# base.net
KiCad netlist of a schematic drawn in EAGLE
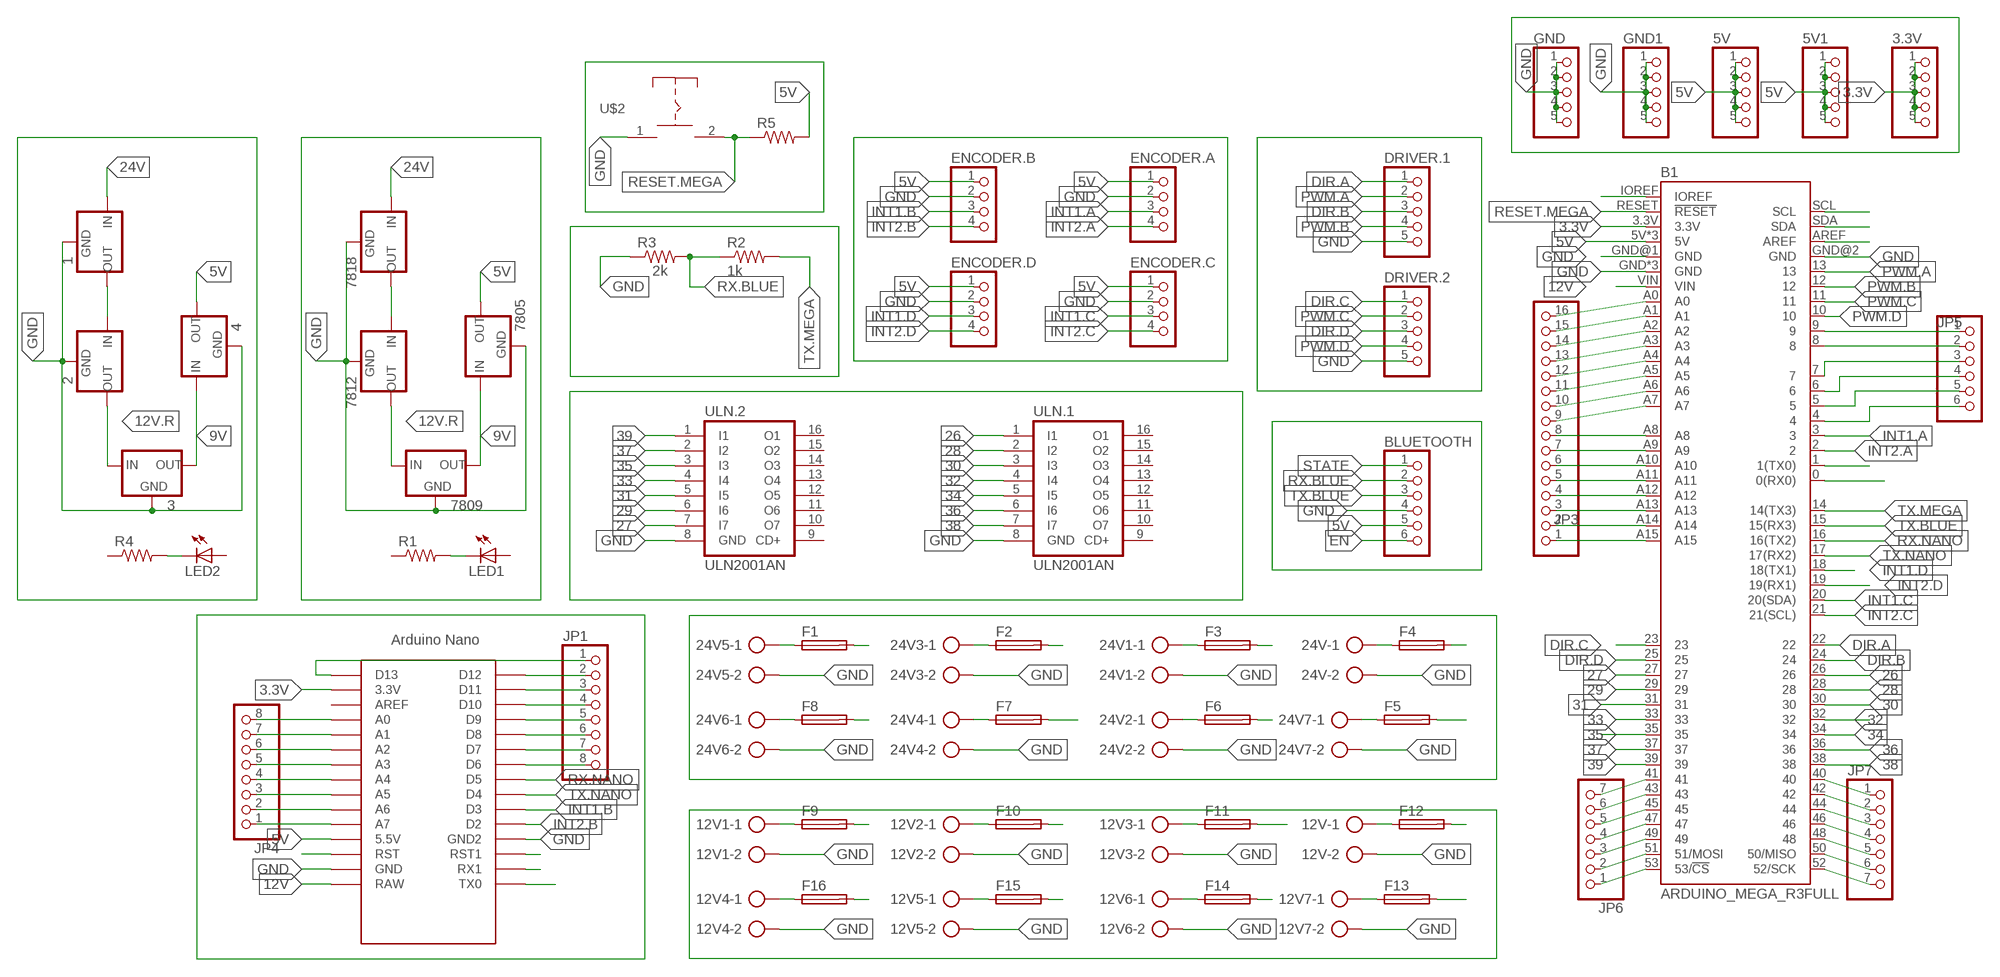
[diagram p0: schematic, sheet 1]

(export (version "E")
  (design (tool "Eeschema 10.0.6"))
  (components
    (comp (ref "1")
      (value "78XXS")
      (footprint "eagle-import:78XXS")
      (libsource (lib "eagle-import") (part "78XXS"))
    )
    (comp (ref "2")
      (value "78XXS")
      (footprint "eagle-import:78XXS")
      (libsource (lib "eagle-import") (part "78XXS"))
    )
    (comp (ref "3")
      (value "78XXS")
      (footprint "eagle-import:78XXS")
      (libsource (lib "eagle-import") (part "78XXS"))
    )
    (comp (ref "3.3V")
      (value "PINHD-1X5")
      (footprint "eagle-import:1X05")
      (libsource (lib "eagle-import") (part "PINHD-1X5"))
    )
    (comp (ref "4")
      (value "78XXS")
      (footprint "eagle-import:78XXS")
      (libsource (lib "eagle-import") (part "78XXS"))
    )
    (comp (ref "5V")
      (value "PINHD-1X5")
      (footprint "eagle-import:1X05")
      (libsource (lib "eagle-import") (part "PINHD-1X5"))
    )
    (comp (ref "5V1")
      (value "PINHD-1X5")
      (footprint "eagle-import:1X05")
      (libsource (lib "eagle-import") (part "PINHD-1X5"))
    )
    (comp (ref "12V")
      (value "AK300/2")
      (footprint "eagle-import:AK300_2")
      (libsource (lib "eagle-import") (part "AK300/2"))
    )
    (comp (ref "12V1")
      (value "AK300/2")
      (footprint "eagle-import:AK300_2")
      (libsource (lib "eagle-import") (part "AK300/2"))
    )
    (comp (ref "12V2")
      (value "AK300/2")
      (footprint "eagle-import:AK300_2")
      (libsource (lib "eagle-import") (part "AK300/2"))
    )
    (comp (ref "12V3")
      (value "AK300/2")
      (footprint "eagle-import:AK300_2")
      (libsource (lib "eagle-import") (part "AK300/2"))
    )
    (comp (ref "12V4")
      (value "AK300/2")
      (footprint "eagle-import:AK300_2")
      (libsource (lib "eagle-import") (part "AK300/2"))
    )
    (comp (ref "12V5")
      (value "AK300/2")
      (footprint "eagle-import:AK300_2")
      (libsource (lib "eagle-import") (part "AK300/2"))
    )
    (comp (ref "12V6")
      (value "AK300/2")
      (footprint "eagle-import:AK300_2")
      (libsource (lib "eagle-import") (part "AK300/2"))
    )
    (comp (ref "12V7")
      (value "AK300/2")
      (footprint "eagle-import:AK300_2")
      (libsource (lib "eagle-import") (part "AK300/2"))
    )
    (comp (ref "24V")
      (value "AK300/2")
      (footprint "eagle-import:AK300_2")
      (libsource (lib "eagle-import") (part "AK300/2"))
    )
    (comp (ref "24V1")
      (value "AK300/2")
      (footprint "eagle-import:AK300_2")
      (libsource (lib "eagle-import") (part "AK300/2"))
    )
    (comp (ref "24V2")
      (value "AK300/2")
      (footprint "eagle-import:AK300_2")
      (libsource (lib "eagle-import") (part "AK300/2"))
    )
    (comp (ref "24V3")
      (value "AK300/2")
      (footprint "eagle-import:AK300_2")
      (libsource (lib "eagle-import") (part "AK300/2"))
    )
    (comp (ref "24V4")
      (value "AK300/2")
      (footprint "eagle-import:AK300_2")
      (libsource (lib "eagle-import") (part "AK300/2"))
    )
    (comp (ref "24V5")
      (value "AK300/2")
      (footprint "eagle-import:AK300_2")
      (libsource (lib "eagle-import") (part "AK300/2"))
    )
    (comp (ref "24V6")
      (value "AK300/2")
      (footprint "eagle-import:AK300_2")
      (libsource (lib "eagle-import") (part "AK300/2"))
    )
    (comp (ref "24V7")
      (value "AK300/2")
      (footprint "eagle-import:AK300_2")
      (libsource (lib "eagle-import") (part "AK300/2"))
    )
    (comp (ref "7805")
      (value "78XXS")
      (footprint "eagle-import:78XXS")
      (libsource (lib "eagle-import") (part "78XXS"))
    )
    (comp (ref "7809")
      (value "78XXS")
      (footprint "eagle-import:78XXS")
      (libsource (lib "eagle-import") (part "78XXS"))
    )
    (comp (ref "7812")
      (value "78XXS")
      (footprint "eagle-import:78XXS")
      (libsource (lib "eagle-import") (part "78XXS"))
    )
    (comp (ref "7818")
      (value "78XXS")
      (footprint "eagle-import:78XXS")
      (libsource (lib "eagle-import") (part "78XXS"))
    )
    (comp (ref "B1")
      (value "ARDUINO_MEGA_R3FULL")
      (footprint "eagle-import:ARDUINO_MEGA_NO_SILK")
      (libsource (lib "eagle-import") (part "ARDUINO_MEGA_R3FULL"))
    )
    (comp (ref "BLUETOOTH")
      (value "PINHD-1X6")
      (footprint "eagle-import:1X06")
      (libsource (lib "eagle-import") (part "PINHD-1X6"))
    )
    (comp (ref "DRIVER.1")
      (value "PINHD-1X5")
      (footprint "eagle-import:1X05")
      (libsource (lib "eagle-import") (part "PINHD-1X5"))
    )
    (comp (ref "DRIVER.2")
      (value "PINHD-1X5")
      (footprint "eagle-import:1X05")
      (libsource (lib "eagle-import") (part "PINHD-1X5"))
    )
    (comp (ref "ENCODER.A")
      (value "PINHD-1X4")
      (footprint "eagle-import:1X04")
      (libsource (lib "eagle-import") (part "PINHD-1X4"))
    )
    (comp (ref "ENCODER.B")
      (value "PINHD-1X4")
      (footprint "eagle-import:1X04")
      (libsource (lib "eagle-import") (part "PINHD-1X4"))
    )
    (comp (ref "ENCODER.C")
      (value "PINHD-1X4")
      (footprint "eagle-import:1X04")
      (libsource (lib "eagle-import") (part "PINHD-1X4"))
    )
    (comp (ref "ENCODER.D")
      (value "PINHD-1X4")
      (footprint "eagle-import:1X04")
      (libsource (lib "eagle-import") (part "PINHD-1X4"))
    )
    (comp (ref "F1")
      (value "GSH15")
      (footprint "eagle-import:GSH15")
      (fields (field (name "MPN") "64900001039"))
      (libsource (lib "eagle-import") (part "GSH15"))
    )
    (comp (ref "F2")
      (value "GSH15")
      (footprint "eagle-import:GSH15")
      (fields (field (name "MPN") "64900001039"))
      (libsource (lib "eagle-import") (part "GSH15"))
    )
    (comp (ref "F3")
      (value "GSH15")
      (footprint "eagle-import:GSH15")
      (fields (field (name "MPN") "64900001039"))
      (libsource (lib "eagle-import") (part "GSH15"))
    )
    (comp (ref "F4")
      (value "GSH15")
      (footprint "eagle-import:GSH15")
      (fields (field (name "MPN") "64900001039"))
      (libsource (lib "eagle-import") (part "GSH15"))
    )
    (comp (ref "F5")
      (value "GSH15")
      (footprint "eagle-import:GSH15")
      (fields (field (name "MPN") "64900001039"))
      (libsource (lib "eagle-import") (part "GSH15"))
    )
    (comp (ref "F6")
      (value "GSH15")
      (footprint "eagle-import:GSH15")
      (fields (field (name "MPN") "64900001039"))
      (libsource (lib "eagle-import") (part "GSH15"))
    )
    (comp (ref "F7")
      (value "GSH15")
      (footprint "eagle-import:GSH15")
      (fields (field (name "MPN") "64900001039"))
      (libsource (lib "eagle-import") (part "GSH15"))
    )
    (comp (ref "F8")
      (value "GSH15")
      (footprint "eagle-import:GSH15")
      (fields (field (name "MPN") "64900001039"))
      (libsource (lib "eagle-import") (part "GSH15"))
    )
    (comp (ref "F9")
      (value "GSH15")
      (footprint "eagle-import:GSH15")
      (fields (field (name "MPN") "64900001039"))
      (libsource (lib "eagle-import") (part "GSH15"))
    )
    (comp (ref "F10")
      (value "GSH15")
      (footprint "eagle-import:GSH15")
      (fields (field (name "MPN") "64900001039"))
      (libsource (lib "eagle-import") (part "GSH15"))
    )
    (comp (ref "F11")
      (value "GSH15")
      (footprint "eagle-import:GSH15")
      (fields (field (name "MPN") "64900001039"))
      (libsource (lib "eagle-import") (part "GSH15"))
    )
    (comp (ref "F12")
      (value "GSH15")
      (footprint "eagle-import:GSH15")
      (fields (field (name "MPN") "64900001039"))
      (libsource (lib "eagle-import") (part "GSH15"))
    )
    (comp (ref "F13")
      (value "GSH15")
      (footprint "eagle-import:GSH15")
      (fields (field (name "MPN") "64900001039"))
      (libsource (lib "eagle-import") (part "GSH15"))
    )
    (comp (ref "F14")
      (value "GSH15")
      (footprint "eagle-import:GSH15")
      (fields (field (name "MPN") "64900001039"))
      (libsource (lib "eagle-import") (part "GSH15"))
    )
    (comp (ref "F15")
      (value "GSH15")
      (footprint "eagle-import:GSH15")
      (fields (field (name "MPN") "64900001039"))
      (libsource (lib "eagle-import") (part "GSH15"))
    )
    (comp (ref "F16")
      (value "GSH15")
      (footprint "eagle-import:GSH15")
      (fields (field (name "MPN") "64900001039"))
      (libsource (lib "eagle-import") (part "GSH15"))
    )
    (comp (ref "GND")
      (value "PINHD-1X5")
      (footprint "eagle-import:1X05")
      (libsource (lib "eagle-import") (part "PINHD-1X5"))
    )
    (comp (ref "GND1")
      (value "PINHD-1X5")
      (footprint "eagle-import:1X05")
      (libsource (lib "eagle-import") (part "PINHD-1X5"))
    )
    (comp (ref "JP1")
      (value "PINHD-1X8")
      (footprint "eagle-import:1X08")
      (libsource (lib "eagle-import") (part "PINHD-1X8"))
    )
    (comp (ref "JP3")
      (value "PINHD-1X16")
      (footprint "eagle-import:1X16")
      (libsource (lib "eagle-import") (part "PINHD-1X16"))
    )
    (comp (ref "JP4")
      (value "PINHD-1X8")
      (footprint "eagle-import:1X08")
      (libsource (lib "eagle-import") (part "PINHD-1X8"))
    )
    (comp (ref "JP5")
      (value "PINHD-1X6")
      (footprint "eagle-import:1X06")
      (libsource (lib "eagle-import") (part "PINHD-1X6"))
    )
    (comp (ref "JP6")
      (value "PINHD-1X7")
      (footprint "eagle-import:1X07")
      (libsource (lib "eagle-import") (part "PINHD-1X7"))
    )
    (comp (ref "JP7")
      (value "PINHD-1X7")
      (footprint "eagle-import:1X07")
      (libsource (lib "eagle-import") (part "PINHD-1X7"))
    )
    (comp (ref "LED1")
      (value "LED5MM")
      (footprint "eagle-import:LED5MM")
      (libsource (lib "eagle-import") (part "LED5MM"))
    )
    (comp (ref "LED2")
      (value "LED5MM")
      (footprint "eagle-import:LED5MM")
      (libsource (lib "eagle-import") (part "LED5MM"))
    )
    (comp (ref "R1")
      (value "R-US_0204/7")
      (footprint "eagle-import:0204_7")
      (libsource (lib "eagle-import") (part "R-US_0204/7"))
    )
    (comp (ref "R2")
      (value "1k")
      (footprint "eagle-import:0204_7")
      (libsource (lib "eagle-import") (part "R-US_0204/7"))
    )
    (comp (ref "R3")
      (value "2k")
      (footprint "eagle-import:0207_10")
      (libsource (lib "eagle-import") (part "R-US_0207/10"))
    )
    (comp (ref "R4")
      (value "R-US_0204/7")
      (footprint "eagle-import:0204_7")
      (libsource (lib "eagle-import") (part "R-US_0204/7"))
    )
    (comp (ref "R5")
      (value "R-US_0204/7")
      (footprint "eagle-import:0204_7")
      (libsource (lib "eagle-import") (part "R-US_0204/7"))
    )
    (comp (ref "U$1")
      (value "NANO")
      (footprint "eagle-import:NANO")
      (libsource (lib "eagle-import") (part "NANO"))
    )
    (comp (ref "U$2")
      (value "PUSHBOTTON")
      (footprint "eagle-import:PUSHBOTTON")
      (libsource (lib "eagle-import") (part "PUSHBOTTON"))
    )
    (comp (ref "ULN.1")
      (value "ULN2001AN")
      (footprint "eagle-import:DIL16")
      (libsource (lib "eagle-import") (part "ULN2001AN"))
    )
    (comp (ref "ULN.2")
      (value "ULN2001AN")
      (footprint "eagle-import:DIL16")
      (libsource (lib "eagle-import") (part "ULN2001AN"))
    )
  )
  (nets
    (net (code "1") (name "3.3V") (class "Default")
      (node (ref "3.3V") (pin "1") (pinfunction "1_1") (pintype "passive"))
      (node (ref "3.3V") (pin "2") (pinfunction "2_2") (pintype "passive"))
      (node (ref "3.3V") (pin "3") (pinfunction "3_3") (pintype "passive"))
      (node (ref "3.3V") (pin "4") (pinfunction "4_4") (pintype "passive"))
      (node (ref "3.3V") (pin "5") (pinfunction "5_5") (pintype "passive"))
      (node (ref "B1") (pin "3.3V") (pinfunction "3.3V_3.3V") (pintype "bidirectional"))
      (node (ref "U$1") (pin "3.3V") (pinfunction "3.3V_3.3V") (pintype "bidirectional"))
    )
    (net (code "2") (name "5V") (class "Default")
      (node (ref "4") (pin "OUT") (pinfunction "OUT_OUT") (pintype "passive"))
      (node (ref "5V") (pin "1") (pinfunction "1_1") (pintype "passive"))
      (node (ref "5V") (pin "2") (pinfunction "2_2") (pintype "passive"))
      (node (ref "5V") (pin "3") (pinfunction "3_3") (pintype "passive"))
      (node (ref "5V") (pin "4") (pinfunction "4_4") (pintype "passive"))
      (node (ref "5V") (pin "5") (pinfunction "5_5") (pintype "passive"))
      (node (ref "5V1") (pin "1") (pinfunction "1_1") (pintype "passive"))
      (node (ref "5V1") (pin "2") (pinfunction "2_2") (pintype "passive"))
      (node (ref "5V1") (pin "3") (pinfunction "3_3") (pintype "passive"))
      (node (ref "5V1") (pin "4") (pinfunction "4_4") (pintype "passive"))
      (node (ref "5V1") (pin "5") (pinfunction "5_5") (pintype "passive"))
      (node (ref "7805") (pin "OUT") (pinfunction "OUT_OUT") (pintype "passive"))
      (node (ref "B1") (pin "5V") (pinfunction "5V_5V") (pintype "bidirectional"))
      (node (ref "B1") (pin "5V@1") (pinfunction "5V_5V@1") (pintype "bidirectional"))
      (node (ref "B1") (pin "5V@2") (pinfunction "5V_5V@2") (pintype "bidirectional"))
      (node (ref "BLUETOOTH") (pin "5") (pinfunction "5_5") (pintype "passive"))
      (node (ref "ENCODER.A") (pin "1") (pinfunction "1_1") (pintype "passive"))
      (node (ref "ENCODER.B") (pin "1") (pinfunction "1_1") (pintype "passive"))
      (node (ref "ENCODER.C") (pin "1") (pinfunction "1_1") (pintype "passive"))
      (node (ref "ENCODER.D") (pin "1") (pinfunction "1_1") (pintype "passive"))
      (node (ref "R5") (pin "2") (pinfunction "2_2") (pintype "passive"))
      (node (ref "U$1") (pin "5V") (pinfunction "5.5V_5V") (pintype "bidirectional"))
    )
    (net (code "3") (name "9V") (class "Default")
      (node (ref "3") (pin "OUT") (pinfunction "OUT_OUT") (pintype "passive"))
      (node (ref "4") (pin "IN") (pinfunction "IN_IN") (pintype "input"))
      (node (ref "7805") (pin "IN") (pinfunction "IN_IN") (pintype "input"))
      (node (ref "7809") (pin "OUT") (pinfunction "OUT_OUT") (pintype "passive"))
    )
    (net (code "4") (name "12V") (class "Default")
      (node (ref "B1") (pin "VIN") (pinfunction "VIN_VIN") (pintype "bidirectional"))
      (node (ref "U$1") (pin "RAW") (pinfunction "RAW_RAW") (pintype "bidirectional"))
    )
    (net (code "5") (name "12V.R") (class "Default")
      (node (ref "2") (pin "OUT") (pinfunction "OUT_OUT") (pintype "passive"))
      (node (ref "3") (pin "IN") (pinfunction "IN_IN") (pintype "input"))
      (node (ref "7809") (pin "IN") (pinfunction "IN_IN") (pintype "input"))
      (node (ref "7812") (pin "OUT") (pinfunction "OUT_OUT") (pintype "passive"))
    )
    (net (code "6") (name "24V") (class "Default")
      (node (ref "1") (pin "IN") (pinfunction "IN_IN") (pintype "input"))
      (node (ref "7818") (pin "IN") (pinfunction "IN_IN") (pintype "input"))
    )
    (net (code "7") (name "26") (class "Default")
      (node (ref "B1") (pin "26") (pinfunction "26_26") (pintype "bidirectional"))
      (node (ref "ULN.1") (pin "1") (pinfunction "I1_1") (pintype "input"))
    )
    (net (code "8") (name "27") (class "Default")
      (node (ref "B1") (pin "27") (pinfunction "27_27") (pintype "bidirectional"))
      (node (ref "ULN.2") (pin "7") (pinfunction "I7_7") (pintype "input"))
    )
    (net (code "9") (name "28") (class "Default")
      (node (ref "B1") (pin "28") (pinfunction "28_28") (pintype "bidirectional"))
      (node (ref "ULN.1") (pin "2") (pinfunction "I2_2") (pintype "input"))
    )
    (net (code "10") (name "29") (class "Default")
      (node (ref "B1") (pin "29") (pinfunction "29_29") (pintype "bidirectional"))
      (node (ref "ULN.2") (pin "6") (pinfunction "I6_6") (pintype "input"))
    )
    (net (code "11") (name "30") (class "Default")
      (node (ref "B1") (pin "30") (pinfunction "30_30") (pintype "bidirectional"))
      (node (ref "ULN.1") (pin "3") (pinfunction "I3_3") (pintype "input"))
    )
    (net (code "12") (name "31") (class "Default")
      (node (ref "B1") (pin "31") (pinfunction "31_31") (pintype "bidirectional"))
      (node (ref "ULN.2") (pin "5") (pinfunction "I5_5") (pintype "input"))
    )
    (net (code "13") (name "32") (class "Default")
      (node (ref "B1") (pin "32") (pinfunction "32_32") (pintype "bidirectional"))
      (node (ref "ULN.1") (pin "4") (pinfunction "I4_4") (pintype "input"))
    )
    (net (code "14") (name "33") (class "Default")
      (node (ref "B1") (pin "33") (pinfunction "33_33") (pintype "bidirectional"))
      (node (ref "ULN.2") (pin "4") (pinfunction "I4_4") (pintype "input"))
    )
    (net (code "15") (name "34") (class "Default")
      (node (ref "B1") (pin "34") (pinfunction "34_34") (pintype "bidirectional"))
      (node (ref "ULN.1") (pin "5") (pinfunction "I5_5") (pintype "input"))
    )
    (net (code "16") (name "35") (class "Default")
      (node (ref "B1") (pin "35") (pinfunction "35_35") (pintype "bidirectional"))
      (node (ref "ULN.2") (pin "3") (pinfunction "I3_3") (pintype "input"))
    )
    (net (code "17") (name "36") (class "Default")
      (node (ref "B1") (pin "36") (pinfunction "36_36") (pintype "bidirectional"))
      (node (ref "ULN.1") (pin "6") (pinfunction "I6_6") (pintype "input"))
    )
    (net (code "18") (name "37") (class "Default")
      (node (ref "B1") (pin "37") (pinfunction "37_37") (pintype "bidirectional"))
      (node (ref "ULN.2") (pin "2") (pinfunction "I2_2") (pintype "input"))
    )
    (net (code "19") (name "38") (class "Default")
      (node (ref "B1") (pin "38") (pinfunction "38_38") (pintype "bidirectional"))
      (node (ref "ULN.1") (pin "7") (pinfunction "I7_7") (pintype "input"))
    )
    (net (code "20") (name "39") (class "Default")
      (node (ref "B1") (pin "39") (pinfunction "39_39") (pintype "bidirectional"))
      (node (ref "ULN.2") (pin "1") (pinfunction "I1_1") (pintype "input"))
    )
    (net (code "21") (name "DIR.A") (class "Default")
      (node (ref "B1") (pin "22") (pinfunction "22_22") (pintype "bidirectional"))
      (node (ref "DRIVER.1") (pin "1") (pinfunction "1_1") (pintype "passive"))
    )
    (net (code "22") (name "DIR.B") (class "Default")
      (node (ref "B1") (pin "24") (pinfunction "24_24") (pintype "bidirectional"))
      (node (ref "DRIVER.1") (pin "3") (pinfunction "3_3") (pintype "passive"))
    )
    (net (code "23") (name "DIR.C") (class "Default")
      (node (ref "B1") (pin "23") (pinfunction "23_23") (pintype "bidirectional"))
      (node (ref "DRIVER.2") (pin "1") (pinfunction "1_1") (pintype "passive"))
    )
    (net (code "24") (name "DIR.D") (class "Default")
      (node (ref "B1") (pin "25") (pinfunction "25_25") (pintype "bidirectional"))
      (node (ref "DRIVER.2") (pin "3") (pinfunction "3_3") (pintype "passive"))
    )
    (net (code "25") (name "EN") (class "Default")
      (node (ref "BLUETOOTH") (pin "6") (pinfunction "6_6") (pintype "passive"))
    )
    (net (code "26") (name "GND") (class "Default")
      (node (ref "1") (pin "GND") (pinfunction "GND_GND") (pintype "input"))
      (node (ref "12V") (pin "2") (pinfunction "KL_2") (pintype "passive"))
      (node (ref "12V1") (pin "2") (pinfunction "KL_2") (pintype "passive"))
      (node (ref "12V2") (pin "2") (pinfunction "KL_2") (pintype "passive"))
      (node (ref "12V3") (pin "2") (pinfunction "KL_2") (pintype "passive"))
      (node (ref "12V4") (pin "2") (pinfunction "KL_2") (pintype "passive"))
      (node (ref "12V5") (pin "2") (pinfunction "KL_2") (pintype "passive"))
      (node (ref "12V6") (pin "2") (pinfunction "KL_2") (pintype "passive"))
      (node (ref "12V7") (pin "2") (pinfunction "KL_2") (pintype "passive"))
      (node (ref "2") (pin "GND") (pinfunction "GND_GND") (pintype "input"))
      (node (ref "24V") (pin "2") (pinfunction "KL_2") (pintype "passive"))
      (node (ref "24V1") (pin "2") (pinfunction "KL_2") (pintype "passive"))
      (node (ref "24V2") (pin "2") (pinfunction "KL_2") (pintype "passive"))
      (node (ref "24V3") (pin "2") (pinfunction "KL_2") (pintype "passive"))
      (node (ref "24V4") (pin "2") (pinfunction "KL_2") (pintype "passive"))
      (node (ref "24V5") (pin "2") (pinfunction "KL_2") (pintype "passive"))
      (node (ref "24V6") (pin "2") (pinfunction "KL_2") (pintype "passive"))
      (node (ref "24V7") (pin "2") (pinfunction "KL_2") (pintype "passive"))
      (node (ref "3") (pin "GND") (pinfunction "GND_GND") (pintype "input"))
      (node (ref "4") (pin "GND") (pinfunction "GND_GND") (pintype "input"))
      (node (ref "7805") (pin "GND") (pinfunction "GND_GND") (pintype "input"))
      (node (ref "7809") (pin "GND") (pinfunction "GND_GND") (pintype "input"))
      (node (ref "7812") (pin "GND") (pinfunction "GND_GND") (pintype "input"))
      (node (ref "7818") (pin "GND") (pinfunction "GND_GND") (pintype "input"))
      (node (ref "B1") (pin "GND") (pinfunction "GND_GND") (pintype "bidirectional"))
      (node (ref "B1") (pin "GND@1") (pinfunction "GND_GND@1") (pintype "bidirectional"))
      (node (ref "B1") (pin "GND@2") (pinfunction "GND_GND@2") (pintype "bidirectional"))
      (node (ref "B1") (pin "GND@3") (pinfunction "GND_GND@3") (pintype "bidirectional"))
      (node (ref "B1") (pin "GND@4") (pinfunction "GND_GND@4") (pintype "bidirectional"))
      (node (ref "BLUETOOTH") (pin "4") (pinfunction "4_4") (pintype "passive"))
      (node (ref "DRIVER.1") (pin "5") (pinfunction "5_5") (pintype "passive"))
      (node (ref "DRIVER.2") (pin "5") (pinfunction "5_5") (pintype "passive"))
      (node (ref "ENCODER.A") (pin "2") (pinfunction "2_2") (pintype "passive"))
      (node (ref "ENCODER.B") (pin "2") (pinfunction "2_2") (pintype "passive"))
      (node (ref "ENCODER.C") (pin "2") (pinfunction "2_2") (pintype "passive"))
      (node (ref "ENCODER.D") (pin "2") (pinfunction "2_2") (pintype "passive"))
      (node (ref "GND") (pin "1") (pinfunction "1_1") (pintype "passive"))
      (node (ref "GND") (pin "2") (pinfunction "2_2") (pintype "passive"))
      (node (ref "GND") (pin "3") (pinfunction "3_3") (pintype "passive"))
      (node (ref "GND") (pin "4") (pinfunction "4_4") (pintype "passive"))
      (node (ref "GND") (pin "5") (pinfunction "5_5") (pintype "passive"))
      (node (ref "GND1") (pin "1") (pinfunction "1_1") (pintype "passive"))
      (node (ref "GND1") (pin "2") (pinfunction "2_2") (pintype "passive"))
      (node (ref "GND1") (pin "3") (pinfunction "3_3") (pintype "passive"))
      (node (ref "GND1") (pin "4") (pinfunction "4_4") (pintype "passive"))
      (node (ref "GND1") (pin "5") (pinfunction "5_5") (pintype "passive"))
      (node (ref "R3") (pin "1") (pinfunction "1_1") (pintype "passive"))
      (node (ref "U$1") (pin "GND") (pinfunction "GND_GND") (pintype "bidirectional"))
      (node (ref "U$1") (pin "GND1") (pinfunction "GND2_GND1") (pintype "bidirectional"))
      (node (ref "U$2") (pin "1") (pinfunction "1_1") (pintype "bidirectional"))
      (node (ref "ULN.1") (pin "8") (pinfunction "GND_8") (pintype "power_in"))
      (node (ref "ULN.2") (pin "8") (pinfunction "GND_8") (pintype "power_in"))
    )
    (net (code "27") (name "INT1.A") (class "Default")
      (node (ref "B1") (pin "3") (pinfunction "3_3") (pintype "bidirectional"))
      (node (ref "ENCODER.A") (pin "3") (pinfunction "3_3") (pintype "passive"))
    )
    (net (code "28") (name "INT1.B") (class "Default")
      (node (ref "ENCODER.B") (pin "3") (pinfunction "3_3") (pintype "passive"))
      (node (ref "U$1") (pin "D3") (pinfunction "D3_D3") (pintype "bidirectional"))
    )
    (net (code "29") (name "INT1.C") (class "Default")
      (node (ref "B1") (pin "20") (pinfunction "20(SDA)_20") (pintype "bidirectional"))
      (node (ref "ENCODER.C") (pin "3") (pinfunction "3_3") (pintype "passive"))
    )
    (net (code "30") (name "INT1.D") (class "Default")
      (node (ref "B1") (pin "18") (pinfunction "18(TX1)_18") (pintype "bidirectional"))
      (node (ref "ENCODER.D") (pin "3") (pinfunction "3_3") (pintype "passive"))
    )
    (net (code "31") (name "INT2.A") (class "Default")
      (node (ref "B1") (pin "2") (pinfunction "2_2") (pintype "bidirectional"))
      (node (ref "ENCODER.A") (pin "4") (pinfunction "4_4") (pintype "passive"))
    )
    (net (code "32") (name "INT2.B") (class "Default")
      (node (ref "ENCODER.B") (pin "4") (pinfunction "4_4") (pintype "passive"))
      (node (ref "U$1") (pin "D2") (pinfunction "D2_D2") (pintype "bidirectional"))
    )
    (net (code "33") (name "INT2.C") (class "Default")
      (node (ref "B1") (pin "21") (pinfunction "21(SCL)_21") (pintype "bidirectional"))
      (node (ref "ENCODER.C") (pin "4") (pinfunction "4_4") (pintype "passive"))
    )
    (net (code "34") (name "INT2.D") (class "Default")
      (node (ref "B1") (pin "19") (pinfunction "19(RX1)_19") (pintype "bidirectional"))
      (node (ref "ENCODER.D") (pin "4") (pinfunction "4_4") (pintype "passive"))
    )
    (net (code "35") (name "Net-(1-PadOUT)") (class "Default")
      (node (ref "1") (pin "OUT") (pinfunction "OUT_OUT") (pintype "passive"))
      (node (ref "2") (pin "IN") (pinfunction "IN_IN") (pintype "input"))
    )
    (net (code "36") (name "Net-(12V1A-KL)") (class "Default")
      (node (ref "12V1") (pin "1") (pinfunction "KL_1") (pintype "passive"))
      (node (ref "F9") (pin "1") (pinfunction "1_1") (pintype "passive"))
    )
    (net (code "37") (name "Net-(12V2A-KL)") (class "Default")
      (node (ref "12V2") (pin "1") (pinfunction "KL_1") (pintype "passive"))
      (node (ref "F10") (pin "1") (pinfunction "1_1") (pintype "passive"))
    )
    (net (code "38") (name "Net-(12V3A-KL)") (class "Default")
      (node (ref "12V3") (pin "1") (pinfunction "KL_1") (pintype "passive"))
      (node (ref "F11") (pin "1") (pinfunction "1_1") (pintype "passive"))
    )
    (net (code "39") (name "Net-(12V4A-KL)") (class "Default")
      (node (ref "12V4") (pin "1") (pinfunction "KL_1") (pintype "passive"))
      (node (ref "F16") (pin "1") (pinfunction "1_1") (pintype "passive"))
    )
    (net (code "40") (name "Net-(12V5A-KL)") (class "Default")
      (node (ref "12V5") (pin "1") (pinfunction "KL_1") (pintype "passive"))
      (node (ref "F15") (pin "1") (pinfunction "1_1") (pintype "passive"))
    )
    (net (code "41") (name "Net-(12V6A-KL)") (class "Default")
      (node (ref "12V6") (pin "1") (pinfunction "KL_1") (pintype "passive"))
      (node (ref "F14") (pin "1") (pinfunction "1_1") (pintype "passive"))
    )
    (net (code "42") (name "Net-(12V7A-KL)") (class "Default")
      (node (ref "12V7") (pin "1") (pinfunction "KL_1") (pintype "passive"))
      (node (ref "F13") (pin "1") (pinfunction "1_1") (pintype "passive"))
    )
    (net (code "43") (name "Net-(12VA-KL)") (class "Default")
      (node (ref "12V") (pin "1") (pinfunction "KL_1") (pintype "passive"))
      (node (ref "F12") (pin "1") (pinfunction "1_1") (pintype "passive"))
    )
    (net (code "44") (name "Net-(24V1A-KL)") (class "Default")
      (node (ref "24V1") (pin "1") (pinfunction "KL_1") (pintype "passive"))
      (node (ref "F3") (pin "1") (pinfunction "1_1") (pintype "passive"))
    )
    (net (code "45") (name "Net-(24V2A-KL)") (class "Default")
      (node (ref "24V2") (pin "1") (pinfunction "KL_1") (pintype "passive"))
      (node (ref "F6") (pin "1") (pinfunction "1_1") (pintype "passive"))
    )
    (net (code "46") (name "Net-(24V3A-KL)") (class "Default")
      (node (ref "24V3") (pin "1") (pinfunction "KL_1") (pintype "passive"))
      (node (ref "F2") (pin "1") (pinfunction "1_1") (pintype "passive"))
    )
    (net (code "47") (name "Net-(24V4A-KL)") (class "Default")
      (node (ref "24V4") (pin "1") (pinfunction "KL_1") (pintype "passive"))
      (node (ref "F7") (pin "1") (pinfunction "1_1") (pintype "passive"))
    )
    (net (code "48") (name "Net-(24V5A-KL)") (class "Default")
      (node (ref "24V5") (pin "1") (pinfunction "KL_1") (pintype "passive"))
      (node (ref "F1") (pin "1") (pinfunction "1_1") (pintype "passive"))
    )
    (net (code "49") (name "Net-(24V6A-KL)") (class "Default")
      (node (ref "24V6") (pin "1") (pinfunction "KL_1") (pintype "passive"))
      (node (ref "F8") (pin "1") (pinfunction "1_1") (pintype "passive"))
    )
    (net (code "50") (name "Net-(24V7A-KL)") (class "Default")
      (node (ref "24V7") (pin "1") (pinfunction "KL_1") (pintype "passive"))
      (node (ref "F5") (pin "1") (pinfunction "1_1") (pintype "passive"))
    )
    (net (code "51") (name "Net-(24VA-KL)") (class "Default")
      (node (ref "24V") (pin "1") (pinfunction "KL_1") (pintype "passive"))
      (node (ref "F4") (pin "1") (pinfunction "1_1") (pintype "passive"))
    )
    (net (code "52") (name "Net-(7812-PadIN)") (class "Default")
      (node (ref "7812") (pin "IN") (pinfunction "IN_IN") (pintype "input"))
      (node (ref "7818") (pin "OUT") (pinfunction "OUT_OUT") (pintype "passive"))
    )
    (net (code "53") (name "Net-(B1-50{slash}MISO)") (class "Default")
      (node (ref "B1") (pin "50") (pinfunction "50/MISO_50") (pintype "bidirectional"))
      (node (ref "JP7") (pin "6") (pinfunction "6_6") (pintype "passive"))
    )
    (net (code "54") (name "Net-(B1-51{slash}MOSI)") (class "Default")
      (node (ref "B1") (pin "51") (pinfunction "51/MOSI_51") (pintype "bidirectional"))
      (node (ref "JP6") (pin "2") (pinfunction "2_2") (pintype "passive"))
    )
    (net (code "55") (name "Net-(B1-52{slash}SCK)") (class "Default")
      (node (ref "B1") (pin "52") (pinfunction "52/SCK_52") (pintype "bidirectional"))
      (node (ref "JP7") (pin "7") (pinfunction "7_7") (pintype "passive"))
    )
    (net (code "56") (name "Net-(B1-53{slash}~{CS})") (class "Default")
      (node (ref "B1") (pin "53") (pinfunction "53/~{CS}_53") (pintype "bidirectional"))
      (node (ref "JP6") (pin "1") (pinfunction "1_1") (pintype "passive"))
    )
    (net (code "57") (name "Net-(B1-Pad4)") (class "Default")
      (node (ref "B1") (pin "4") (pinfunction "4_4") (pintype "bidirectional"))
      (node (ref "JP5") (pin "6") (pinfunction "6_6") (pintype "passive"))
    )
    (net (code "58") (name "Net-(B1-Pad5)") (class "Default")
      (node (ref "B1") (pin "5") (pinfunction "5_5") (pintype "bidirectional"))
      (node (ref "JP5") (pin "5") (pinfunction "5_5") (pintype "passive"))
    )
    (net (code "59") (name "Net-(B1-Pad6)") (class "Default")
      (node (ref "B1") (pin "6") (pinfunction "6_6") (pintype "bidirectional"))
      (node (ref "JP5") (pin "4") (pinfunction "4_4") (pintype "passive"))
    )
    (net (code "60") (name "Net-(B1-Pad7)") (class "Default")
      (node (ref "B1") (pin "7") (pinfunction "7_7") (pintype "bidirectional"))
      (node (ref "JP5") (pin "3") (pinfunction "3_3") (pintype "passive"))
    )
    (net (code "61") (name "Net-(B1-Pad8)") (class "Default")
      (node (ref "B1") (pin "8") (pinfunction "8_8") (pintype "bidirectional"))
      (node (ref "JP5") (pin "2") (pinfunction "2_2") (pintype "passive"))
    )
    (net (code "62") (name "Net-(B1-Pad9)") (class "Default")
      (node (ref "B1") (pin "9") (pinfunction "9_9") (pintype "bidirectional"))
      (node (ref "JP5") (pin "1") (pinfunction "1_1") (pintype "passive"))
    )
    (net (code "63") (name "Net-(B1-Pad40)") (class "Default")
      (node (ref "B1") (pin "40") (pinfunction "40_40") (pintype "bidirectional"))
      (node (ref "JP7") (pin "1") (pinfunction "1_1") (pintype "passive"))
    )
    (net (code "64") (name "Net-(B1-Pad41)") (class "Default")
      (node (ref "B1") (pin "41") (pinfunction "41_41") (pintype "bidirectional"))
      (node (ref "JP6") (pin "7") (pinfunction "7_7") (pintype "passive"))
    )
    (net (code "65") (name "Net-(B1-Pad42)") (class "Default")
      (node (ref "B1") (pin "42") (pinfunction "42_42") (pintype "bidirectional"))
      (node (ref "JP7") (pin "2") (pinfunction "2_2") (pintype "passive"))
    )
    (net (code "66") (name "Net-(B1-Pad43)") (class "Default")
      (node (ref "B1") (pin "43") (pinfunction "43_43") (pintype "bidirectional"))
      (node (ref "JP6") (pin "6") (pinfunction "6_6") (pintype "passive"))
    )
    (net (code "67") (name "Net-(B1-Pad44)") (class "Default")
      (node (ref "B1") (pin "44") (pinfunction "44_44") (pintype "bidirectional"))
      (node (ref "JP7") (pin "3") (pinfunction "3_3") (pintype "passive"))
    )
    (net (code "68") (name "Net-(B1-Pad45)") (class "Default")
      (node (ref "B1") (pin "45") (pinfunction "45_45") (pintype "bidirectional"))
      (node (ref "JP6") (pin "5") (pinfunction "5_5") (pintype "passive"))
    )
    (net (code "69") (name "Net-(B1-Pad46)") (class "Default")
      (node (ref "B1") (pin "46") (pinfunction "46_46") (pintype "bidirectional"))
      (node (ref "JP7") (pin "4") (pinfunction "4_4") (pintype "passive"))
    )
    (net (code "70") (name "Net-(B1-Pad47)") (class "Default")
      (node (ref "B1") (pin "47") (pinfunction "47_47") (pintype "bidirectional"))
      (node (ref "JP6") (pin "4") (pinfunction "4_4") (pintype "passive"))
    )
    (net (code "71") (name "Net-(B1-Pad48)") (class "Default")
      (node (ref "B1") (pin "48") (pinfunction "48_48") (pintype "bidirectional"))
      (node (ref "JP7") (pin "5") (pinfunction "5_5") (pintype "passive"))
    )
    (net (code "72") (name "Net-(B1-Pad49)") (class "Default")
      (node (ref "B1") (pin "49") (pinfunction "49_49") (pintype "bidirectional"))
      (node (ref "JP6") (pin "3") (pinfunction "3_3") (pintype "passive"))
    )
    (net (code "73") (name "Net-(B1-PadA0)") (class "Default")
      (node (ref "B1") (pin "A0") (pinfunction "A0_A0") (pintype "bidirectional"))
      (node (ref "JP3") (pin "16") (pinfunction "16_16") (pintype "passive"))
    )
    (net (code "74") (name "Net-(B1-PadA1)") (class "Default")
      (node (ref "B1") (pin "A1") (pinfunction "A1_A1") (pintype "bidirectional"))
      (node (ref "JP3") (pin "15") (pinfunction "15_15") (pintype "passive"))
    )
    (net (code "75") (name "Net-(B1-PadA2)") (class "Default")
      (node (ref "B1") (pin "A2") (pinfunction "A2_A2") (pintype "bidirectional"))
      (node (ref "JP3") (pin "14") (pinfunction "14_14") (pintype "passive"))
    )
    (net (code "76") (name "Net-(B1-PadA3)") (class "Default")
      (node (ref "B1") (pin "A3") (pinfunction "A3_A3") (pintype "bidirectional"))
      (node (ref "JP3") (pin "13") (pinfunction "13_13") (pintype "passive"))
    )
    (net (code "77") (name "Net-(B1-PadA4)") (class "Default")
      (node (ref "B1") (pin "A4") (pinfunction "A4_A4") (pintype "bidirectional"))
      (node (ref "JP3") (pin "12") (pinfunction "12_12") (pintype "passive"))
    )
    (net (code "78") (name "Net-(B1-PadA5)") (class "Default")
      (node (ref "B1") (pin "A5") (pinfunction "A5_A5") (pintype "bidirectional"))
      (node (ref "JP3") (pin "11") (pinfunction "11_11") (pintype "passive"))
    )
    (net (code "79") (name "Net-(B1-PadA6)") (class "Default")
      (node (ref "B1") (pin "A6") (pinfunction "A6_A6") (pintype "bidirectional"))
      (node (ref "JP3") (pin "10") (pinfunction "10_10") (pintype "passive"))
    )
    (net (code "80") (name "Net-(B1-PadA7)") (class "Default")
      (node (ref "B1") (pin "A7") (pinfunction "A7_A7") (pintype "bidirectional"))
      (node (ref "JP3") (pin "9") (pinfunction "9_9") (pintype "passive"))
    )
    (net (code "81") (name "Net-(B1-PadA8)") (class "Default")
      (node (ref "B1") (pin "A8") (pinfunction "A8_A8") (pintype "bidirectional"))
      (node (ref "JP3") (pin "8") (pinfunction "8_8") (pintype "passive"))
    )
    (net (code "82") (name "Net-(B1-PadA9)") (class "Default")
      (node (ref "B1") (pin "A9") (pinfunction "A9_A9") (pintype "bidirectional"))
      (node (ref "JP3") (pin "7") (pinfunction "7_7") (pintype "passive"))
    )
    (net (code "83") (name "Net-(B1-PadA10)") (class "Default")
      (node (ref "B1") (pin "A10") (pinfunction "A10_A10") (pintype "bidirectional"))
      (node (ref "JP3") (pin "6") (pinfunction "6_6") (pintype "passive"))
    )
    (net (code "84") (name "Net-(B1-PadA11)") (class "Default")
      (node (ref "B1") (pin "A11") (pinfunction "A11_A11") (pintype "bidirectional"))
      (node (ref "JP3") (pin "5") (pinfunction "5_5") (pintype "passive"))
    )
    (net (code "85") (name "Net-(B1-PadA12)") (class "Default")
      (node (ref "B1") (pin "A12") (pinfunction "A12_A12") (pintype "bidirectional"))
      (node (ref "JP3") (pin "4") (pinfunction "4_4") (pintype "passive"))
    )
    (net (code "86") (name "Net-(B1-PadA13)") (class "Default")
      (node (ref "B1") (pin "A13") (pinfunction "A13_A13") (pintype "bidirectional"))
      (node (ref "JP3") (pin "3") (pinfunction "3_3") (pintype "passive"))
    )
    (net (code "87") (name "Net-(B1-PadA14)") (class "Default")
      (node (ref "B1") (pin "A14") (pinfunction "A14_A14") (pintype "bidirectional"))
      (node (ref "JP3") (pin "2") (pinfunction "2_2") (pintype "passive"))
    )
    (net (code "88") (name "Net-(B1-PadA15)") (class "Default")
      (node (ref "B1") (pin "A15") (pinfunction "A15_A15") (pintype "bidirectional"))
      (node (ref "JP3") (pin "1") (pinfunction "1_1") (pintype "passive"))
    )
    (net (code "89") (name "Net-(JP1-Pad1)") (class "Default")
      (node (ref "JP1") (pin "1") (pinfunction "1_1") (pintype "passive"))
      (node (ref "U$1") (pin "D13") (pinfunction "D13_D13") (pintype "bidirectional"))
    )
    (net (code "90") (name "Net-(JP1-Pad2)") (class "Default")
      (node (ref "JP1") (pin "2") (pinfunction "2_2") (pintype "passive"))
      (node (ref "U$1") (pin "D12") (pinfunction "D12_D12") (pintype "bidirectional"))
    )
    (net (code "91") (name "Net-(JP1-Pad3)") (class "Default")
      (node (ref "JP1") (pin "3") (pinfunction "3_3") (pintype "passive"))
      (node (ref "U$1") (pin "D11") (pinfunction "D11_D11") (pintype "bidirectional"))
    )
    (net (code "92") (name "Net-(JP1-Pad4)") (class "Default")
      (node (ref "JP1") (pin "4") (pinfunction "4_4") (pintype "passive"))
      (node (ref "U$1") (pin "D10") (pinfunction "D10_D10") (pintype "bidirectional"))
    )
    (net (code "93") (name "Net-(JP1-Pad5)") (class "Default")
      (node (ref "JP1") (pin "5") (pinfunction "5_5") (pintype "passive"))
      (node (ref "U$1") (pin "D9") (pinfunction "D9_D9") (pintype "bidirectional"))
    )
    (net (code "94") (name "Net-(JP1-Pad6)") (class "Default")
      (node (ref "JP1") (pin "6") (pinfunction "6_6") (pintype "passive"))
      (node (ref "U$1") (pin "D8") (pinfunction "D8_D8") (pintype "bidirectional"))
    )
    (net (code "95") (name "Net-(JP1-Pad7)") (class "Default")
      (node (ref "JP1") (pin "7") (pinfunction "7_7") (pintype "passive"))
      (node (ref "U$1") (pin "D7") (pinfunction "D7_D7") (pintype "bidirectional"))
    )
    (net (code "96") (name "Net-(JP1-Pad8)") (class "Default")
      (node (ref "JP1") (pin "8") (pinfunction "8_8") (pintype "passive"))
      (node (ref "U$1") (pin "D6") (pinfunction "D6_D6") (pintype "bidirectional"))
    )
    (net (code "97") (name "Net-(JP4-Pad1)") (class "Default")
      (node (ref "JP4") (pin "1") (pinfunction "1_1") (pintype "passive"))
      (node (ref "U$1") (pin "A7") (pinfunction "A7_A7") (pintype "bidirectional"))
    )
    (net (code "98") (name "Net-(JP4-Pad2)") (class "Default")
      (node (ref "JP4") (pin "2") (pinfunction "2_2") (pintype "passive"))
      (node (ref "U$1") (pin "A6") (pinfunction "A6_A6") (pintype "bidirectional"))
    )
    (net (code "99") (name "Net-(JP4-Pad3)") (class "Default")
      (node (ref "JP4") (pin "3") (pinfunction "3_3") (pintype "passive"))
      (node (ref "U$1") (pin "A5") (pinfunction "A5_A5") (pintype "bidirectional"))
    )
    (net (code "100") (name "Net-(JP4-Pad4)") (class "Default")
      (node (ref "JP4") (pin "4") (pinfunction "4_4") (pintype "passive"))
      (node (ref "U$1") (pin "A4") (pinfunction "A4_A4") (pintype "bidirectional"))
    )
    (net (code "101") (name "Net-(JP4-Pad5)") (class "Default")
      (node (ref "JP4") (pin "5") (pinfunction "5_5") (pintype "passive"))
      (node (ref "U$1") (pin "A3") (pinfunction "A3_A3") (pintype "bidirectional"))
    )
    (net (code "102") (name "Net-(JP4-Pad6)") (class "Default")
      (node (ref "JP4") (pin "6") (pinfunction "6_6") (pintype "passive"))
      (node (ref "U$1") (pin "A2") (pinfunction "A2_A2") (pintype "bidirectional"))
    )
    (net (code "103") (name "Net-(JP4-Pad7)") (class "Default")
      (node (ref "JP4") (pin "7") (pinfunction "7_7") (pintype "passive"))
      (node (ref "U$1") (pin "A1") (pinfunction "A1_A1") (pintype "bidirectional"))
    )
    (net (code "104") (name "Net-(JP4-Pad8)") (class "Default")
      (node (ref "JP4") (pin "8") (pinfunction "8_8") (pintype "passive"))
      (node (ref "U$1") (pin "A0") (pinfunction "A0_A0") (pintype "bidirectional"))
    )
    (net (code "105") (name "Net-(LED1-C)") (class "Default")
      (node (ref "LED1") (pin "K") (pinfunction "C_K") (pintype "passive"))
      (node (ref "R1") (pin "2") (pinfunction "2_2") (pintype "passive"))
    )
    (net (code "106") (name "Net-(LED2-C)") (class "Default")
      (node (ref "LED2") (pin "K") (pinfunction "C_K") (pintype "passive"))
      (node (ref "R4") (pin "2") (pinfunction "2_2") (pintype "passive"))
    )
    (net (code "107") (name "PWM.A") (class "Default")
      (node (ref "B1") (pin "13") (pinfunction "13_13") (pintype "bidirectional"))
      (node (ref "DRIVER.1") (pin "2") (pinfunction "2_2") (pintype "passive"))
    )
    (net (code "108") (name "PWM.B") (class "Default")
      (node (ref "B1") (pin "12") (pinfunction "12_12") (pintype "bidirectional"))
      (node (ref "DRIVER.1") (pin "4") (pinfunction "4_4") (pintype "passive"))
    )
    (net (code "109") (name "PWM.C") (class "Default")
      (node (ref "B1") (pin "11") (pinfunction "11_11") (pintype "bidirectional"))
      (node (ref "DRIVER.2") (pin "2") (pinfunction "2_2") (pintype "passive"))
    )
    (net (code "110") (name "PWM.D") (class "Default")
      (node (ref "B1") (pin "10") (pinfunction "10_10") (pintype "bidirectional"))
      (node (ref "DRIVER.2") (pin "4") (pinfunction "4_4") (pintype "passive"))
    )
    (net (code "111") (name "RESET.MEGA") (class "Default")
      (node (ref "B1") (pin "RESET") (pinfunction "~{RESET}_RESET") (pintype "bidirectional"))
      (node (ref "R5") (pin "1") (pinfunction "1_1") (pintype "passive"))
      (node (ref "U$2") (pin "2") (pinfunction "2_2") (pintype "bidirectional"))
    )
    (net (code "112") (name "RX.BLUE") (class "Default")
      (node (ref "BLUETOOTH") (pin "2") (pinfunction "2_2") (pintype "passive"))
      (node (ref "R2") (pin "1") (pinfunction "1_1") (pintype "passive"))
      (node (ref "R3") (pin "2") (pinfunction "2_2") (pintype "passive"))
    )
    (net (code "113") (name "RX.NANO") (class "Default")
      (node (ref "B1") (pin "16") (pinfunction "16(TX2)_16") (pintype "bidirectional"))
      (node (ref "U$1") (pin "D5") (pinfunction "D5_D5") (pintype "bidirectional"))
    )
    (net (code "114") (name "STATE") (class "Default")
      (node (ref "BLUETOOTH") (pin "1") (pinfunction "1_1") (pintype "passive"))
    )
    (net (code "115") (name "TX.BLUE") (class "Default")
      (node (ref "B1") (pin "15") (pinfunction "15(RX3)_15") (pintype "bidirectional"))
      (node (ref "BLUETOOTH") (pin "3") (pinfunction "3_3") (pintype "passive"))
    )
    (net (code "116") (name "TX.MEGA") (class "Default")
      (node (ref "B1") (pin "14") (pinfunction "14(TX3)_14") (pintype "bidirectional"))
      (node (ref "R2") (pin "2") (pinfunction "2_2") (pintype "passive"))
    )
    (net (code "117") (name "TX.NANO") (class "Default")
      (node (ref "B1") (pin "17") (pinfunction "17(RX2)_17") (pintype "bidirectional"))
      (node (ref "U$1") (pin "D4") (pinfunction "D4_D4") (pintype "bidirectional"))
    )
    (net (code "118") (name "unconnected-(B1-0(RX0)-Pad0)") (class "Default")
      (node (ref "B1") (pin "0") (pinfunction "0(RX0)_0") (pintype "bidirectional"))
    )
    (net (code "119") (name "unconnected-(B1-1(TX0)-Pad1)") (class "Default")
      (node (ref "B1") (pin "1") (pinfunction "1(TX0)_1") (pintype "bidirectional"))
    )
    (net (code "120") (name "unconnected-(B1-PadAREF)") (class "Default")
      (node (ref "B1") (pin "AREF") (pinfunction "AREF_AREF") (pintype "bidirectional"))
    )
    (net (code "121") (name "unconnected-(B1-PadIOREF)") (class "Default")
      (node (ref "B1") (pin "IOREF") (pinfunction "IOREF_IOREF") (pintype "bidirectional"))
    )
    (net (code "122") (name "unconnected-(B1-PadSCL)") (class "Default")
      (node (ref "B1") (pin "SCL") (pinfunction "SCL_SCL") (pintype "bidirectional"))
    )
    (net (code "123") (name "unconnected-(B1-PadSDA)") (class "Default")
      (node (ref "B1") (pin "SDA") (pinfunction "SDA_SDA") (pintype "bidirectional"))
    )
    (net (code "124") (name "unconnected-(F1-Pad2)") (class "Default")
      (node (ref "F1") (pin "2") (pinfunction "2_2") (pintype "passive"))
    )
    (net (code "125") (name "unconnected-(F2-Pad2)") (class "Default")
      (node (ref "F2") (pin "2") (pinfunction "2_2") (pintype "passive"))
    )
    (net (code "126") (name "unconnected-(F3-Pad2)") (class "Default")
      (node (ref "F3") (pin "2") (pinfunction "2_2") (pintype "passive"))
    )
    (net (code "127") (name "unconnected-(F4-Pad2)") (class "Default")
      (node (ref "F4") (pin "2") (pinfunction "2_2") (pintype "passive"))
    )
    (net (code "128") (name "unconnected-(F5-Pad2)") (class "Default")
      (node (ref "F5") (pin "2") (pinfunction "2_2") (pintype "passive"))
    )
    (net (code "129") (name "unconnected-(F6-Pad2)") (class "Default")
      (node (ref "F6") (pin "2") (pinfunction "2_2") (pintype "passive"))
    )
    (net (code "130") (name "unconnected-(F7-Pad2)") (class "Default")
      (node (ref "F7") (pin "2") (pinfunction "2_2") (pintype "passive"))
    )
    (net (code "131") (name "unconnected-(F8-Pad2)") (class "Default")
      (node (ref "F8") (pin "2") (pinfunction "2_2") (pintype "passive"))
    )
    (net (code "132") (name "unconnected-(F9-Pad2)") (class "Default")
      (node (ref "F9") (pin "2") (pinfunction "2_2") (pintype "passive"))
    )
    (net (code "133") (name "unconnected-(F10-Pad2)") (class "Default")
      (node (ref "F10") (pin "2") (pinfunction "2_2") (pintype "passive"))
    )
    (net (code "134") (name "unconnected-(F11-Pad2)") (class "Default")
      (node (ref "F11") (pin "2") (pinfunction "2_2") (pintype "passive"))
    )
    (net (code "135") (name "unconnected-(F12-Pad2)") (class "Default")
      (node (ref "F12") (pin "2") (pinfunction "2_2") (pintype "passive"))
    )
    (net (code "136") (name "unconnected-(F13-Pad2)") (class "Default")
      (node (ref "F13") (pin "2") (pinfunction "2_2") (pintype "passive"))
    )
    (net (code "137") (name "unconnected-(F14-Pad2)") (class "Default")
      (node (ref "F14") (pin "2") (pinfunction "2_2") (pintype "passive"))
    )
    (net (code "138") (name "unconnected-(F15-Pad2)") (class "Default")
      (node (ref "F15") (pin "2") (pinfunction "2_2") (pintype "passive"))
    )
    (net (code "139") (name "unconnected-(F16-Pad2)") (class "Default")
      (node (ref "F16") (pin "2") (pinfunction "2_2") (pintype "passive"))
    )
    (net (code "140") (name "unconnected-(LED1-PadA)") (class "Default")
      (node (ref "LED1") (pin "A") (pinfunction "A_A") (pintype "passive"))
    )
    (net (code "141") (name "unconnected-(LED2-PadA)") (class "Default")
      (node (ref "LED2") (pin "A") (pinfunction "A_A") (pintype "passive"))
    )
    (net (code "142") (name "unconnected-(R1-Pad1)") (class "Default")
      (node (ref "R1") (pin "1") (pinfunction "1_1") (pintype "passive"))
    )
    (net (code "143") (name "unconnected-(R4-Pad1)") (class "Default")
      (node (ref "R4") (pin "1") (pinfunction "1_1") (pintype "passive"))
    )
    (net (code "144") (name "unconnected-(U$1-PadAREF)") (class "Default")
      (node (ref "U$1") (pin "AREF") (pinfunction "AREF_AREF") (pintype "bidirectional"))
    )
    (net (code "145") (name "unconnected-(U$1-PadRST)") (class "Default")
      (node (ref "U$1") (pin "RST") (pinfunction "RST_RST") (pintype "bidirectional"))
    )
    (net (code "146") (name "unconnected-(U$1-PadRST1)") (class "Default")
      (node (ref "U$1") (pin "RST1") (pinfunction "RST1_RST1") (pintype "bidirectional"))
    )
    (net (code "147") (name "unconnected-(U$1-PadRX1)") (class "Default")
      (node (ref "U$1") (pin "RX1") (pinfunction "RX1_RX1") (pintype "bidirectional"))
    )
    (net (code "148") (name "unconnected-(U$1-PadTX0)") (class "Default")
      (node (ref "U$1") (pin "TX0") (pinfunction "TX0_TX0") (pintype "bidirectional"))
    )
    (net (code "149") (name "unconnected-(ULN.1-CD+-Pad9)") (class "Default")
      (node (ref "ULN.1") (pin "9") (pinfunction "CD+_9") (pintype "passive"))
    )
    (net (code "150") (name "unconnected-(ULN.1-O1-Pad16)") (class "Default")
      (node (ref "ULN.1") (pin "16") (pinfunction "O1_16") (pintype "open_collector"))
    )
    (net (code "151") (name "unconnected-(ULN.1-O2-Pad15)") (class "Default")
      (node (ref "ULN.1") (pin "15") (pinfunction "O2_15") (pintype "open_collector"))
    )
    (net (code "152") (name "unconnected-(ULN.1-O3-Pad14)") (class "Default")
      (node (ref "ULN.1") (pin "14") (pinfunction "O3_14") (pintype "open_collector"))
    )
    (net (code "153") (name "unconnected-(ULN.1-O4-Pad13)") (class "Default")
      (node (ref "ULN.1") (pin "13") (pinfunction "O4_13") (pintype "open_collector"))
    )
    (net (code "154") (name "unconnected-(ULN.1-O5-Pad12)") (class "Default")
      (node (ref "ULN.1") (pin "12") (pinfunction "O5_12") (pintype "open_collector"))
    )
    (net (code "155") (name "unconnected-(ULN.1-O6-Pad11)") (class "Default")
      (node (ref "ULN.1") (pin "11") (pinfunction "O6_11") (pintype "open_collector"))
    )
    (net (code "156") (name "unconnected-(ULN.1-O7-Pad10)") (class "Default")
      (node (ref "ULN.1") (pin "10") (pinfunction "O7_10") (pintype "open_collector"))
    )
    (net (code "157") (name "unconnected-(ULN.2-CD+-Pad9)") (class "Default")
      (node (ref "ULN.2") (pin "9") (pinfunction "CD+_9") (pintype "passive"))
    )
    (net (code "158") (name "unconnected-(ULN.2-O1-Pad16)") (class "Default")
      (node (ref "ULN.2") (pin "16") (pinfunction "O1_16") (pintype "open_collector"))
    )
    (net (code "159") (name "unconnected-(ULN.2-O2-Pad15)") (class "Default")
      (node (ref "ULN.2") (pin "15") (pinfunction "O2_15") (pintype "open_collector"))
    )
    (net (code "160") (name "unconnected-(ULN.2-O3-Pad14)") (class "Default")
      (node (ref "ULN.2") (pin "14") (pinfunction "O3_14") (pintype "open_collector"))
    )
    (net (code "161") (name "unconnected-(ULN.2-O4-Pad13)") (class "Default")
      (node (ref "ULN.2") (pin "13") (pinfunction "O4_13") (pintype "open_collector"))
    )
    (net (code "162") (name "unconnected-(ULN.2-O5-Pad12)") (class "Default")
      (node (ref "ULN.2") (pin "12") (pinfunction "O5_12") (pintype "open_collector"))
    )
    (net (code "163") (name "unconnected-(ULN.2-O6-Pad11)") (class "Default")
      (node (ref "ULN.2") (pin "11") (pinfunction "O6_11") (pintype "open_collector"))
    )
    (net (code "164") (name "unconnected-(ULN.2-O7-Pad10)") (class "Default")
      (node (ref "ULN.2") (pin "10") (pinfunction "O7_10") (pintype "open_collector"))
    )
  )
)
